# Audio_Input_Line_In.net
KiCad netlist of a schematic drawn in Altium Designer
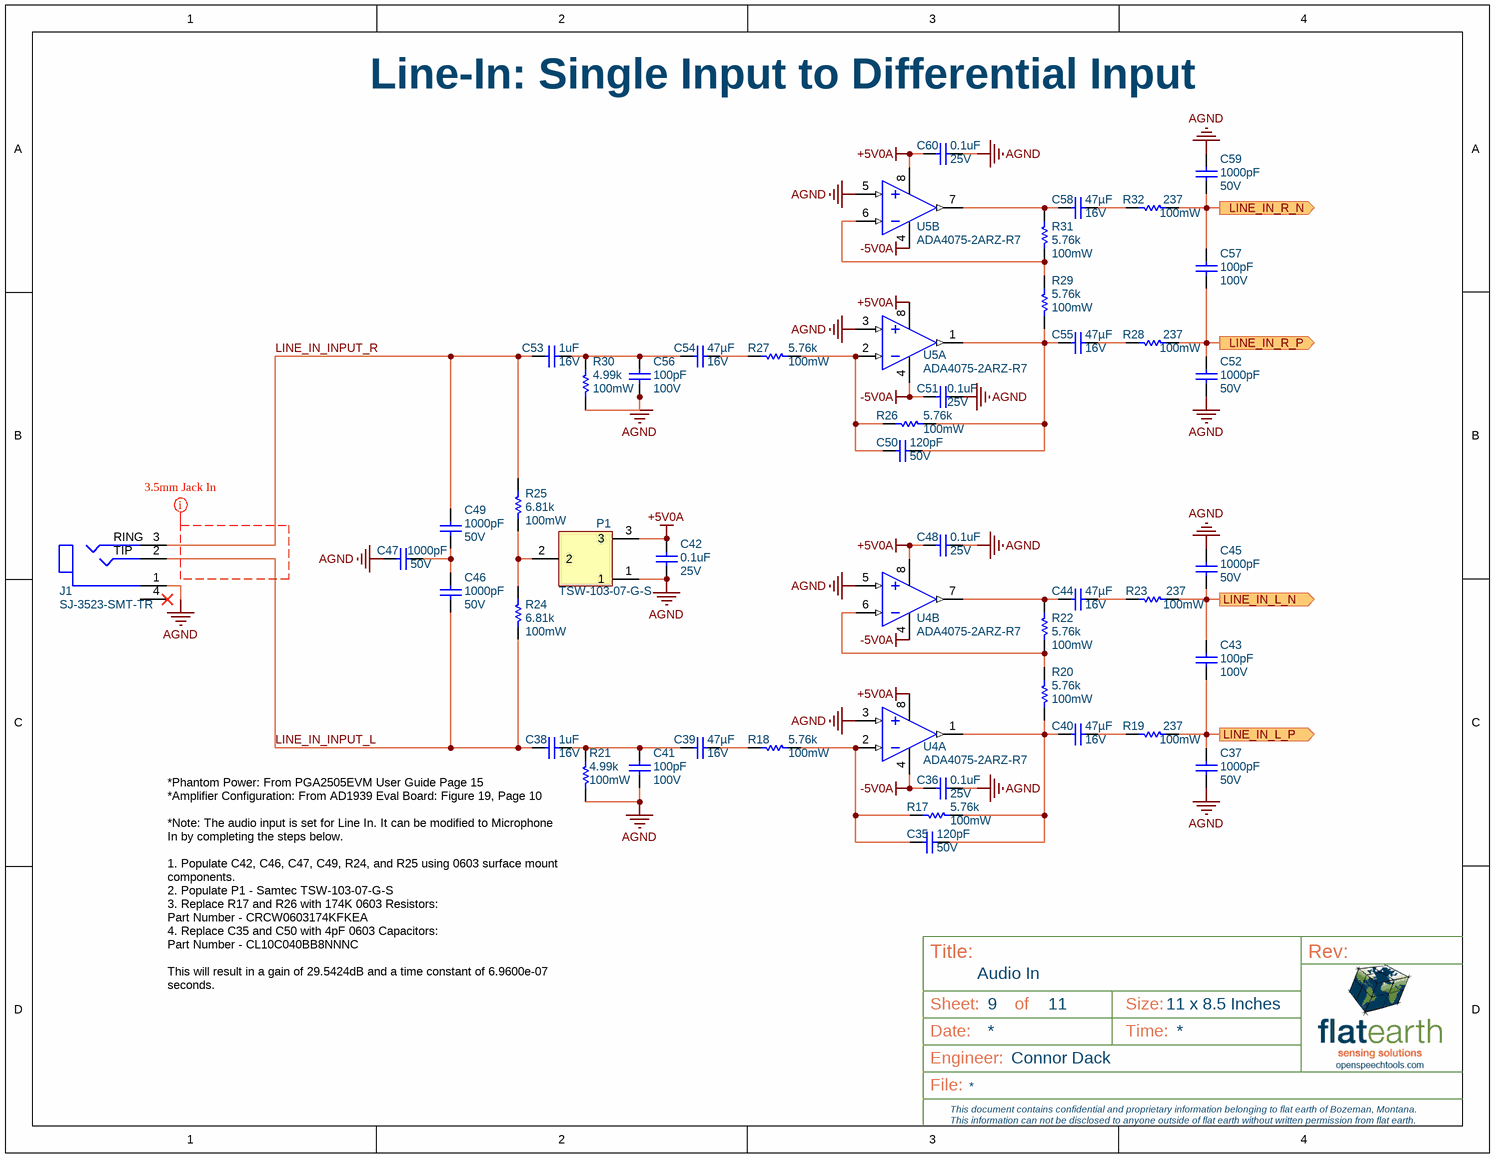
[diagram p0: Audio_Input_Line_In.SchDoc]

(export (version "E")
  (design (tool "Eeschema 10.0.6"))
  (components
    (comp (ref "C35")
      (value "CL10C121JB8NCNC")
      (footprint "3-0603_L")
      (description "120pF 50V Ceramic Capacitor C0G, NP0 0603 (1608 Metric) 0.063\" L x 0.031\" W (1.60mm x 0.80mm)")
      (fields
        (field (name "MANUFACTURER") "Samsung Electro-Mechanics America, Inc.")
        (field (name "TOLERANCE") "±5%")
        (field (name "VOLTAGE - RATED") "50V")
        (field (name "CAPACITANCE") "120pF")
      )
      (libsource (lib "Schematic_Components") (part "CL10C121JB8NCNC"))
    )
    (comp (ref "C36")
      (value "CGA3E2X7R1E104K080AA")
      (footprint "3-0603_L")
      (description "CAP CER 0.1UF 25V X7R 0603")
      (fields
        (field (name "MANUFACTURER") "TDK")
        (field (name "TOLERANCE") "10%")
        (field (name "VOLTAGE RATING") "25V")
        (field (name "CAPACITANCE") "0.1uF")
      )
      (libsource (lib "Schematic_Components_CD") (part "CGA3E2X7R1E104K080AA"))
    )
    (comp (ref "C37")
      (value "CL10B102KB8NNNC")
      (footprint "3-0603_L")
      (description "1000pF 50V Ceramic Capacitor X7R 0603 (1608 Metric) 0.063\" L x 0.031\" W (1.60mm x 0.80mm)")
      (fields
        (field (name "MANUFACTURER") "Samsung Electro-Mechanics America, Inc.")
        (field (name "TOLERANCE") "±10%")
        (field (name "VOLTAGE - RATED") "50V")
        (field (name "CAPACITANCE") "1000pF")
      )
      (libsource (lib "Schematic_Components") (part "CL10B102KB8NNNC"))
    )
    (comp (ref "C38")
      (value "CGA3E1X7R1C105M080AC")
      (footprint "3-0603_L")
      (description "CAP CER 1UF 16V X7R 0603")
      (fields
        (field (name "MANUFACTURER") "TDK")
        (field (name "TOLERANCE") "20%")
        (field (name "VOLTAGE RATING (DC)") "16V")
        (field (name "CAPACITANCE") "1uF")
      )
      (libsource (lib "Schematic_Components_CD") (part "CGA3E1X7R1C105M080AC"))
    )
    (comp (ref "C39")
      (value "GRM32EC81C476KE15L")
      (footprint "C1210X25_L")
      (description "47µF ±10% 16V Ceramic Capacitor X6S 1210 (3225 Metric)")
      (fields
        (field (name "MANUFACTURER") "Murata Electronics North America")
        (field (name "TOLERANCE") "±10%")
        (field (name "VOLTAGE - RATED") "16V")
        (field (name "CAPACITANCE") "47µF")
      )
      (libsource (lib "Schematic_Components") (part "GRM32EC81C476KE15L"))
    )
    (comp (ref "C40")
      (value "GRM32EC81C476KE15L")
      (footprint "C1210X25_L")
      (description "47µF ±10% 16V Ceramic Capacitor X6S 1210 (3225 Metric)")
      (fields
        (field (name "MANUFACTURER") "Murata Electronics North America")
        (field (name "TOLERANCE") "±10%")
        (field (name "VOLTAGE - RATED") "16V")
        (field (name "CAPACITANCE") "47µF")
      )
      (libsource (lib "Schematic_Components") (part "GRM32EC81C476KE15L"))
    )
    (comp (ref "C41")
      (value "C1608C0G2A101J")
      (footprint "3-0603_L")
      (description "CAP CER 100PF 100V 5% NP0 0603")
      (fields
        (field (name "MANUFACTURER") "TDK Corporation")
        (field (name "VOLTAGE - RATED") "100V")
        (field (name "TOLERANCE") "±5%")
        (field (name "CAPACITANCE") "100pF")
      )
      (libsource (lib "Schematic_Components") (part "C1608C0G2A101J"))
    )
    (comp (ref "C42")
      (value "CGA3E2X7R1E104K080AA")
      (footprint "3-0603_L")
      (description "CAP CER 0.1UF 25V X7R 0603")
      (fields
        (field (name "MANUFACTURER") "TDK")
        (field (name "TOLERANCE") "10%")
        (field (name "VOLTAGE RATING") "25V")
        (field (name "CAPACITANCE") "0.1uF")
      )
      (libsource (lib "Schematic_Components_CD") (part "CGA3E2X7R1E104K080AA"))
    )
    (comp (ref "C43")
      (value "C1608C0G2A101J")
      (footprint "3-0603_L")
      (description "CAP CER 100PF 100V 5% NP0 0603")
      (fields
        (field (name "MANUFACTURER") "TDK Corporation")
        (field (name "VOLTAGE - RATED") "100V")
        (field (name "TOLERANCE") "±5%")
        (field (name "CAPACITANCE") "100pF")
      )
      (libsource (lib "Schematic_Components") (part "C1608C0G2A101J"))
    )
    (comp (ref "C44")
      (value "GRM32EC81C476KE15L")
      (footprint "C1210X25_L")
      (description "47µF ±10% 16V Ceramic Capacitor X6S 1210 (3225 Metric)")
      (fields
        (field (name "MANUFACTURER") "Murata Electronics North America")
        (field (name "TOLERANCE") "±10%")
        (field (name "VOLTAGE - RATED") "16V")
        (field (name "CAPACITANCE") "47µF")
      )
      (libsource (lib "Schematic_Components") (part "GRM32EC81C476KE15L"))
    )
    (comp (ref "C45")
      (value "CL10B102KB8NNNC")
      (footprint "3-0603_L")
      (description "1000pF 50V Ceramic Capacitor X7R 0603 (1608 Metric) 0.063\" L x 0.031\" W (1.60mm x 0.80mm)")
      (fields
        (field (name "MANUFACTURER") "Samsung Electro-Mechanics America, Inc.")
        (field (name "TOLERANCE") "±10%")
        (field (name "VOLTAGE - RATED") "50V")
        (field (name "CAPACITANCE") "1000pF")
      )
      (libsource (lib "Schematic_Components") (part "CL10B102KB8NNNC"))
    )
    (comp (ref "C46")
      (value "C1608C0G1H102J")
      (footprint "3-0603_L_DNP")
      (description "CAP CER 1000PF 50V 5% NP0 0603")
      (fields
        (field (name "MANUFACTURER") "TDK Corporation")
        (field (name "VOLTAGE - RATED") "50V")
        (field (name "TOLERANCE") "±5%")
        (field (name "CAPACITANCE") "1000pF")
      )
      (libsource (lib "Schematic_Components") (part "C1608C0G1H102J"))
    )
    (comp (ref "C47")
      (value "C1608C0G1H102J")
      (footprint "3-0603_L_DNP")
      (description "CAP CER 1000PF 50V 5% NP0 0603")
      (fields
        (field (name "MANUFACTURER") "TDK Corporation")
        (field (name "VOLTAGE - RATED") "50V")
        (field (name "TOLERANCE") "±5%")
        (field (name "CAPACITANCE") "1000pF")
      )
      (libsource (lib "Schematic_Components") (part "C1608C0G1H102J"))
    )
    (comp (ref "C48")
      (value "CGA3E2X7R1E104K080AA")
      (footprint "3-0603_L")
      (description "CAP CER 0.1UF 25V X7R 0603")
      (fields
        (field (name "MANUFACTURER") "TDK")
        (field (name "TOLERANCE") "10%")
        (field (name "VOLTAGE RATING") "25V")
        (field (name "CAPACITANCE") "0.1uF")
      )
      (libsource (lib "Schematic_Components_CD") (part "CGA3E2X7R1E104K080AA"))
    )
    (comp (ref "C49")
      (value "C1608C0G1H102J")
      (footprint "3-0603_L_DNP")
      (description "CAP CER 1000PF 50V 5% NP0 0603")
      (fields
        (field (name "MANUFACTURER") "TDK Corporation")
        (field (name "VOLTAGE - RATED") "50V")
        (field (name "TOLERANCE") "±5%")
        (field (name "CAPACITANCE") "1000pF")
      )
      (libsource (lib "Schematic_Components") (part "C1608C0G1H102J"))
    )
    (comp (ref "C50")
      (value "CL10C121JB8NCNC")
      (footprint "3-0603_L")
      (description "120pF 50V Ceramic Capacitor C0G, NP0 0603 (1608 Metric) 0.063\" L x 0.031\" W (1.60mm x 0.80mm)")
      (fields
        (field (name "MANUFACTURER") "Samsung Electro-Mechanics America, Inc.")
        (field (name "TOLERANCE") "±5%")
        (field (name "VOLTAGE - RATED") "50V")
        (field (name "CAPACITANCE") "120pF")
      )
      (libsource (lib "Schematic_Components") (part "CL10C121JB8NCNC"))
    )
    (comp (ref "C51")
      (value "CGA3E2X7R1E104K080AA")
      (footprint "3-0603_L")
      (description "CAP CER 0.1UF 25V X7R 0603")
      (fields
        (field (name "MANUFACTURER") "TDK")
        (field (name "TOLERANCE") "10%")
        (field (name "VOLTAGE RATING") "25V")
        (field (name "CAPACITANCE") "0.1uF")
      )
      (libsource (lib "Schematic_Components_CD") (part "CGA3E2X7R1E104K080AA"))
    )
    (comp (ref "C52")
      (value "CL10B102KB8NNNC")
      (footprint "3-0603_L")
      (description "1000pF 50V Ceramic Capacitor X7R 0603 (1608 Metric) 0.063\" L x 0.031\" W (1.60mm x 0.80mm)")
      (fields
        (field (name "MANUFACTURER") "Samsung Electro-Mechanics America, Inc.")
        (field (name "TOLERANCE") "±10%")
        (field (name "VOLTAGE - RATED") "50V")
        (field (name "CAPACITANCE") "1000pF")
      )
      (libsource (lib "Schematic_Components") (part "CL10B102KB8NNNC"))
    )
    (comp (ref "C53")
      (value "CGA3E1X7R1C105M080AC")
      (footprint "3-0603_L")
      (description "CAP CER 1UF 16V X7R 0603")
      (fields
        (field (name "MANUFACTURER") "TDK")
        (field (name "TOLERANCE") "20%")
        (field (name "VOLTAGE RATING") "16V")
        (field (name "CAPACITANCE") "1uF")
      )
      (libsource (lib "Schematic_Components_CD") (part "CGA3E1X7R1C105M080AC"))
    )
    (comp (ref "C54")
      (value "GRM32EC81C476KE15L")
      (footprint "C1210X25_L")
      (description "47µF ±10% 16V Ceramic Capacitor X6S 1210 (3225 Metric)")
      (fields
        (field (name "MANUFACTURER") "Murata Electronics North America")
        (field (name "TOLERANCE") "±10%")
        (field (name "VOLTAGE - RATED") "16V")
        (field (name "CAPACITANCE") "47µF")
      )
      (libsource (lib "Schematic_Components") (part "GRM32EC81C476KE15L"))
    )
    (comp (ref "C55")
      (value "GRM32EC81C476KE15L")
      (footprint "C1210X25_L")
      (description "47µF ±10% 16V Ceramic Capacitor X6S 1210 (3225 Metric)")
      (fields
        (field (name "MANUFACTURER") "Murata Electronics North America")
        (field (name "TOLERANCE") "±10%")
        (field (name "VOLTAGE - RATED") "16V")
        (field (name "CAPACITANCE") "47µF")
      )
      (libsource (lib "Schematic_Components") (part "GRM32EC81C476KE15L"))
    )
    (comp (ref "C56")
      (value "C1608C0G2A101J")
      (footprint "3-0603_L")
      (description "CAP CER 100PF 100V 5% NP0 0603")
      (fields
        (field (name "MANUFACTURER") "TDK Corporation")
        (field (name "VOLTAGE - RATED") "100V")
        (field (name "TOLERANCE") "±5%")
        (field (name "CAPACITANCE") "100pF")
      )
      (libsource (lib "Schematic_Components") (part "C1608C0G2A101J"))
    )
    (comp (ref "C57")
      (value "C1608C0G2A101J")
      (footprint "3-0603_L")
      (description "CAP CER 100PF 100V 5% NP0 0603")
      (fields
        (field (name "MANUFACTURER") "TDK Corporation")
        (field (name "VOLTAGE - RATED") "100V")
        (field (name "TOLERANCE") "±5%")
        (field (name "CAPACITANCE") "100pF")
      )
      (libsource (lib "Schematic_Components") (part "C1608C0G2A101J"))
    )
    (comp (ref "C58")
      (value "GRM32EC81C476KE15L")
      (footprint "C1210X25_L")
      (description "47µF ±10% 16V Ceramic Capacitor X6S 1210 (3225 Metric)")
      (fields
        (field (name "MANUFACTURER") "Murata Electronics North America")
        (field (name "TOLERANCE") "±10%")
        (field (name "VOLTAGE - RATED") "16V")
        (field (name "CAPACITANCE") "47µF")
      )
      (libsource (lib "Schematic_Components") (part "GRM32EC81C476KE15L"))
    )
    (comp (ref "C59")
      (value "CL10B102KB8NNNC")
      (footprint "3-0603_L")
      (description "1000pF 50V Ceramic Capacitor X7R 0603 (1608 Metric) 0.063\" L x 0.031\" W (1.60mm x 0.80mm)")
      (fields
        (field (name "MANUFACTURER") "Samsung Electro-Mechanics America, Inc.")
        (field (name "TOLERANCE") "±10%")
        (field (name "VOLTAGE - RATED") "50V")
        (field (name "CAPACITANCE") "1000pF")
      )
      (libsource (lib "Schematic_Components") (part "CL10B102KB8NNNC"))
    )
    (comp (ref "C60")
      (value "CGA3E2X7R1E104K080AA")
      (footprint "3-0603_L")
      (description "CAP CER 0.1UF 25V X7R 0603")
      (fields
        (field (name "MANUFACTURER") "TDK")
        (field (name "TOLERANCE") "10%")
        (field (name "VOLTAGE RATING") "25V")
        (field (name "CAPACITANCE") "0.1uF")
      )
      (libsource (lib "Schematic_Components_CD") (part "CGA3E2X7R1E104K080AA"))
    )
    (comp (ref "J1")
      (value "SJ-3523-SMT-TR")
      (footprint "SJ-3523-SMT-TR")
      (description "3.50mm (0.141\", 1/8\", Mini Plug) - Headphone Phone Jack Stereo Connector Solder")
      (fields
        (field (name "MANUFACTURER") "CUI Inc.")
        (field (name "MANUFACTURER PART NUMBER") "SJ-3523-SMT-TR")
        (field (name "PUBLISHER") "Altium Limited")
      )
      (libsource (lib "Schematic_Components_CD") (part "SJ-3523-SMT-TR"))
    )
    (comp (ref "P1")
      (value "TSW-103-07-G-S")
      (footprint "3Pin_Header")
      (description "3 Pin Through Hole Connector with 0.1\" Spacing")
      (fields (field (name "MANUFACTURER") "Samtec") (field (name "PUBLISHER") "Altium Limited"))
      (libsource (lib "Schematic_Components_CD") (part "CONN_TH_3PIN_0D1"))
    )
    (comp (ref "R17")
      (value "ERJ-3EKF5761V")
      (footprint "3-0603_R_L")
      (description "RES SMD 5.76K OHM 1% 1/10W 0603")
      (fields
        (field (name "MANUFACTURER") "Panasonic Electronic Components")
        (field (name "TOLERANCE") "±1%")
        (field (name "POWER (WATTS)") "100mW")
        (field (name "RESISTANCE (OHMS)") "5.76k")
      )
      (libsource (lib "Schematic_Components") (part "ERJ-3EKF5761V"))
    )
    (comp (ref "R18")
      (value "ERJ-3EKF5761V")
      (footprint "3-0603_R_L")
      (description "RES SMD 5.76K OHM 1% 1/10W 0603")
      (fields
        (field (name "MANUFACTURER") "Panasonic Electronic Components")
        (field (name "TOLERANCE") "±1%")
        (field (name "POWER (WATTS)") "100mW")
        (field (name "RESISTANCE (OHMS)") "5.76k")
      )
      (libsource (lib "Schematic_Components") (part "ERJ-3EKF5761V"))
    )
    (comp (ref "R19")
      (value "ERJ-3EKF2370V")
      (footprint "3-0603_R_L")
      (description "RES SMD 237 OHM 1% 1/10W 0603")
      (fields
        (field (name "MANUFACTURER") "Panasonic Electronic Components")
        (field (name "TOLERANCE") "±1%")
        (field (name "POWER (WATTS)") "100mW")
        (field (name "RESISTANCE (OHMS)") "237")
      )
      (libsource (lib "Schematic_Components") (part "ERJ-3EKF2370V"))
    )
    (comp (ref "R20")
      (value "ERJ-3EKF5761V")
      (footprint "3-0603_R_L")
      (description "RES SMD 5.76K OHM 1% 1/10W 0603")
      (fields
        (field (name "MANUFACTURER") "Panasonic Electronic Components")
        (field (name "TOLERANCE") "±1%")
        (field (name "POWER (WATTS)") "100mW")
        (field (name "RESISTANCE (OHMS)") "5.76k")
      )
      (libsource (lib "Schematic_Components") (part "ERJ-3EKF5761V"))
    )
    (comp (ref "R21")
      (value "ERJ-3EKF4991V")
      (footprint "3-0603_R_L")
      (description "RES SMD 4.99K OHM 1% 1/10W 0603")
      (fields
        (field (name "MANUFACTURER") "Panasonic Electronic Components")
        (field (name "TOLERANCE") "±1%")
        (field (name "POWER (WATTS)") "100mW")
        (field (name "RESISTANCE (OHMS)") "4.99k")
      )
      (libsource (lib "Schematic_Components") (part "ERJ-3EKF4991V"))
    )
    (comp (ref "R22")
      (value "ERJ-3EKF5761V")
      (footprint "3-0603_R_L")
      (description "RES SMD 5.76K OHM 1% 1/10W 0603")
      (fields
        (field (name "MANUFACTURER") "Panasonic Electronic Components")
        (field (name "TOLERANCE") "±1%")
        (field (name "POWER (WATTS)") "100mW")
        (field (name "RESISTANCE (OHMS)") "5.76k")
      )
      (libsource (lib "Schematic_Components") (part "ERJ-3EKF5761V"))
    )
    (comp (ref "R23")
      (value "ERJ-3EKF2370V")
      (footprint "3-0603_R_L")
      (description "RES SMD 237 OHM 1% 1/10W 0603")
      (fields
        (field (name "MANUFACTURER") "Panasonic Electronic Components")
        (field (name "TOLERANCE") "±1%")
        (field (name "POWER (WATTS)") "100mW")
        (field (name "RESISTANCE (OHMS)") "237")
      )
      (libsource (lib "Schematic_Components") (part "ERJ-3EKF2370V"))
    )
    (comp (ref "R24")
      (value "ERJ-3EKF6811V")
      (footprint "3-0603_R_L_DNP")
      (description "RES SMD 6.81K OHM 1% 1/10W 0603")
      (fields
        (field (name "MANUFACTURER") "Panasonic ECG")
        (field (name "TOLERANCE") "1%")
        (field (name "POWER RATING") "100mW")
        (field (name "RESISTANCE") "6.81k")
      )
      (libsource (lib "Schematic_Components_CD") (part "ERJ-3EKF6811V"))
    )
    (comp (ref "R25")
      (value "ERJ-3EKF6811V")
      (footprint "3-0603_R_L_DNP")
      (description "RES SMD 6.81K OHM 1% 1/10W 0603")
      (fields
        (field (name "MANUFACTURER") "Panasonic ECG")
        (field (name "TOLERANCE") "1%")
        (field (name "POWER RATING") "100mW")
        (field (name "RESISTANCE") "6.81k")
      )
      (libsource (lib "Schematic_Components_CD") (part "ERJ-3EKF6811V"))
    )
    (comp (ref "R26")
      (value "ERJ-3EKF5761V")
      (footprint "3-0603_R_L")
      (description "RES SMD 5.76K OHM 1% 1/10W 0603")
      (fields
        (field (name "MANUFACTURER") "Panasonic Electronic Components")
        (field (name "TOLERANCE") "±1%")
        (field (name "POWER (WATTS)") "100mW")
        (field (name "RESISTANCE (OHMS)") "5.76k")
      )
      (libsource (lib "Schematic_Components") (part "ERJ-3EKF5761V"))
    )
    (comp (ref "R27")
      (value "ERJ-3EKF5761V")
      (footprint "3-0603_R_L")
      (description "RES SMD 5.76K OHM 1% 1/10W 0603")
      (fields
        (field (name "MANUFACTURER") "Panasonic Electronic Components")
        (field (name "TOLERANCE") "±1%")
        (field (name "POWER (WATTS)") "100mW")
        (field (name "RESISTANCE (OHMS)") "5.76k")
      )
      (libsource (lib "Schematic_Components") (part "ERJ-3EKF5761V"))
    )
    (comp (ref "R28")
      (value "ERJ-3EKF2370V")
      (footprint "3-0603_R_L")
      (description "RES SMD 237 OHM 1% 1/10W 0603")
      (fields
        (field (name "MANUFACTURER") "Panasonic Electronic Components")
        (field (name "TOLERANCE") "±1%")
        (field (name "POWER (WATTS)") "100mW")
        (field (name "RESISTANCE (OHMS)") "237")
      )
      (libsource (lib "Schematic_Components") (part "ERJ-3EKF2370V"))
    )
    (comp (ref "R29")
      (value "ERJ-3EKF5761V")
      (footprint "3-0603_R_L")
      (description "RES SMD 5.76K OHM 1% 1/10W 0603")
      (fields
        (field (name "MANUFACTURER") "Panasonic Electronic Components")
        (field (name "TOLERANCE") "±1%")
        (field (name "POWER (WATTS)") "100mW")
        (field (name "RESISTANCE (OHMS)") "5.76k")
      )
      (libsource (lib "Schematic_Components") (part "ERJ-3EKF5761V"))
    )
    (comp (ref "R30")
      (value "ERJ-3EKF4991V")
      (footprint "3-0603_R_L")
      (description "RES SMD 4.99K OHM 1% 1/10W 0603")
      (fields
        (field (name "MANUFACTURER") "Panasonic Electronic Components")
        (field (name "TOLERANCE") "±1%")
        (field (name "POWER (WATTS)") "100mW")
        (field (name "RESISTANCE (OHMS)") "4.99k")
      )
      (libsource (lib "Schematic_Components") (part "ERJ-3EKF4991V"))
    )
    (comp (ref "R31")
      (value "ERJ-3EKF5761V")
      (footprint "3-0603_R_L")
      (description "RES SMD 5.76K OHM 1% 1/10W 0603")
      (fields
        (field (name "MANUFACTURER") "Panasonic Electronic Components")
        (field (name "TOLERANCE") "±1%")
        (field (name "POWER (WATTS)") "100mW")
        (field (name "RESISTANCE (OHMS)") "5.76k")
      )
      (libsource (lib "Schematic_Components") (part "ERJ-3EKF5761V"))
    )
    (comp (ref "R32")
      (value "ERJ-3EKF2370V")
      (footprint "3-0603_R_L")
      (description "RES SMD 237 OHM 1% 1/10W 0603")
      (fields
        (field (name "MANUFACTURER") "Panasonic Electronic Components")
        (field (name "TOLERANCE") "±1%")
        (field (name "POWER (WATTS)") "100mW")
        (field (name "RESISTANCE (OHMS)") "237")
      )
      (libsource (lib "Schematic_Components") (part "ERJ-3EKF2370V"))
    )
    (comp (ref "U4")
      (value "ADA4075-2ARZ-R7")
      (footprint "SOIC127P600X175-8N")
      (description "IC OPAMP GP 6.5MHZ 8SOIC")
      (fields
        (field (name "MANUFACTURER") "Analog Devices Inc.")
        (field (name "MANUFACTURER PART NUMBER") "ADA4075-2ARZ-R7")
      )
      (libsource (lib "Schematic_Components_CD") (part "ADA4075-2ARZ-R7"))
    )
    (comp (ref "U5")
      (value "ADA4075-2ARZ-R7")
      (footprint "SOIC127P600X175-8N")
      (description "IC OPAMP GP 6.5MHZ 8SOIC")
      (fields
        (field (name "MANUFACTURER") "Analog Devices Inc.")
        (field (name "MANUFACTURER PART NUMBER") "ADA4075-2ARZ-R7")
      )
      (libsource (lib "Schematic_Components_CD") (part "ADA4075-2ARZ-R7"))
    )
  )
  (nets
    (net (code "1") (name "+5V0A") (class "Default")
      (node (ref "C42") (pin "2") (pinfunction "2_2") (pintype "passive"))
      (node (ref "C48") (pin "2") (pinfunction "2_2") (pintype "passive"))
      (node (ref "C60") (pin "2") (pinfunction "2_2") (pintype "passive"))
      (node (ref "P1") (pin "3") (pinfunction "3_3") (pintype "passive"))
      (node (ref "U4") (pin "8") (pinfunction "V+_8") (pintype "passive"))
      (node (ref "U5") (pin "8") (pinfunction "V+_8") (pintype "passive"))
    )
    (net (code "2") (name "-5V0A") (class "Default")
      (node (ref "C36") (pin "2") (pinfunction "2_2") (pintype "passive"))
      (node (ref "C51") (pin "2") (pinfunction "2_2") (pintype "passive"))
      (node (ref "U4") (pin "4") (pinfunction "V-_4") (pintype "power_in"))
      (node (ref "U5") (pin "4") (pinfunction "V-_4") (pintype "power_in"))
    )
    (net (code "3") (name "/LINE_IN_INPUT_L") (class "Default")
      (node (ref "C38") (pin "1") (pinfunction "1_1") (pintype "passive"))
      (node (ref "C46") (pin "2") (pinfunction "2_2") (pintype "passive"))
      (node (ref "J1") (pin "2") (pinfunction "Tip_2") (pintype "passive"))
      (node (ref "R24") (pin "2") (pinfunction "2_2") (pintype "passive"))
    )
    (net (code "4") (name "/LINE_IN_INPUT_R") (class "Default")
      (node (ref "C49") (pin "1") (pinfunction "1_1") (pintype "passive"))
      (node (ref "C53") (pin "1") (pinfunction "1_1") (pintype "passive"))
      (node (ref "J1") (pin "3") (pinfunction "Ring_3") (pintype "passive"))
      (node (ref "R25") (pin "1") (pinfunction "1_1") (pintype "passive"))
    )
    (net (code "5") (name "/LINE_IN_L_N") (class "Default")
      (node (ref "C43") (pin "1") (pinfunction "1_1") (pintype "passive"))
      (node (ref "C45") (pin "2") (pinfunction "2_2") (pintype "passive"))
      (node (ref "R23") (pin "2") (pinfunction "2_2") (pintype "passive"))
    )
    (net (code "6") (name "/LINE_IN_L_P") (class "Default")
      (node (ref "C37") (pin "2") (pinfunction "2_2") (pintype "passive"))
      (node (ref "C43") (pin "2") (pinfunction "2_2") (pintype "passive"))
      (node (ref "R19") (pin "2") (pinfunction "2_2") (pintype "passive"))
    )
    (net (code "7") (name "/LINE_IN_R_N") (class "Default")
      (node (ref "C57") (pin "1") (pinfunction "1_1") (pintype "passive"))
      (node (ref "C59") (pin "2") (pinfunction "2_2") (pintype "passive"))
      (node (ref "R32") (pin "2") (pinfunction "2_2") (pintype "passive"))
    )
    (net (code "8") (name "/LINE_IN_R_P") (class "Default")
      (node (ref "C52") (pin "2") (pinfunction "2_2") (pintype "passive"))
      (node (ref "C57") (pin "2") (pinfunction "2_2") (pintype "passive"))
      (node (ref "R28") (pin "2") (pinfunction "2_2") (pintype "passive"))
    )
    (net (code "9") (name "AGND") (class "Default")
      (node (ref "C36") (pin "1") (pinfunction "1_1") (pintype "passive"))
      (node (ref "C37") (pin "1") (pinfunction "1_1") (pintype "passive"))
      (node (ref "C41") (pin "2") (pinfunction "2_2") (pintype "passive"))
      (node (ref "C42") (pin "1") (pinfunction "1_1") (pintype "passive"))
      (node (ref "C45") (pin "1") (pinfunction "1_1") (pintype "passive"))
      (node (ref "C47") (pin "2") (pinfunction "2_2") (pintype "passive"))
      (node (ref "C48") (pin "1") (pinfunction "1_1") (pintype "passive"))
      (node (ref "C51") (pin "1") (pinfunction "1_1") (pintype "passive"))
      (node (ref "C52") (pin "1") (pinfunction "1_1") (pintype "passive"))
      (node (ref "C56") (pin "2") (pinfunction "2_2") (pintype "passive"))
      (node (ref "C59") (pin "1") (pinfunction "1_1") (pintype "passive"))
      (node (ref "C60") (pin "1") (pinfunction "1_1") (pintype "passive"))
      (node (ref "J1") (pin "1") (pinfunction "Sleeve_1") (pintype "passive"))
      (node (ref "P1") (pin "1") (pinfunction "1_1") (pintype "passive"))
      (node (ref "R21") (pin "1") (pinfunction "1_1") (pintype "passive"))
      (node (ref "R30") (pin "1") (pinfunction "1_1") (pintype "passive"))
      (node (ref "U4") (pin "3") (pinfunction "+INA_3") (pintype "input"))
      (node (ref "U4") (pin "5") (pinfunction "+INB_5") (pintype "input"))
      (node (ref "U5") (pin "3") (pinfunction "+INA_3") (pintype "input"))
      (node (ref "U5") (pin "5") (pinfunction "+INB_5") (pintype "input"))
    )
    (net (code "10") (name "Net-(C38-Pad2)") (class "Default")
      (node (ref "C38") (pin "2") (pinfunction "2_2") (pintype "passive"))
      (node (ref "C39") (pin "1") (pinfunction "1_1") (pintype "passive"))
      (node (ref "C41") (pin "1") (pinfunction "1_1") (pintype "passive"))
      (node (ref "R21") (pin "2") (pinfunction "2_2") (pintype "passive"))
    )
    (net (code "11") (name "Net-(C39-Pad2)") (class "Default")
      (node (ref "C39") (pin "2") (pinfunction "2_2") (pintype "passive"))
      (node (ref "R18") (pin "1") (pinfunction "1_1") (pintype "passive"))
    )
    (net (code "12") (name "Net-(C40-Pad2)") (class "Default")
      (node (ref "C40") (pin "2") (pinfunction "2_2") (pintype "passive"))
      (node (ref "R19") (pin "1") (pinfunction "1_1") (pintype "passive"))
    )
    (net (code "13") (name "Net-(C44-Pad2)") (class "Default")
      (node (ref "C44") (pin "2") (pinfunction "2_2") (pintype "passive"))
      (node (ref "R23") (pin "1") (pinfunction "1_1") (pintype "passive"))
    )
    (net (code "14") (name "Net-(C46-Pad1)") (class "Default")
      (node (ref "C46") (pin "1") (pinfunction "1_1") (pintype "passive"))
      (node (ref "C47") (pin "1") (pinfunction "1_1") (pintype "passive"))
      (node (ref "C49") (pin "2") (pinfunction "2_2") (pintype "passive"))
    )
    (net (code "15") (name "Net-(C53-Pad2)") (class "Default")
      (node (ref "C53") (pin "2") (pinfunction "2_2") (pintype "passive"))
      (node (ref "C54") (pin "1") (pinfunction "1_1") (pintype "passive"))
      (node (ref "C56") (pin "1") (pinfunction "1_1") (pintype "passive"))
      (node (ref "R30") (pin "2") (pinfunction "2_2") (pintype "passive"))
    )
    (net (code "16") (name "Net-(C54-Pad2)") (class "Default")
      (node (ref "C54") (pin "2") (pinfunction "2_2") (pintype "passive"))
      (node (ref "R27") (pin "1") (pinfunction "1_1") (pintype "passive"))
    )
    (net (code "17") (name "Net-(C55-Pad2)") (class "Default")
      (node (ref "C55") (pin "2") (pinfunction "2_2") (pintype "passive"))
      (node (ref "R28") (pin "1") (pinfunction "1_1") (pintype "passive"))
    )
    (net (code "18") (name "Net-(C58-Pad2)") (class "Default")
      (node (ref "C58") (pin "2") (pinfunction "2_2") (pintype "passive"))
      (node (ref "R32") (pin "1") (pinfunction "1_1") (pintype "passive"))
    )
    (net (code "19") (name "Net-(P1-Pad2)") (class "Default")
      (node (ref "P1") (pin "2") (pinfunction "2_2") (pintype "passive"))
      (node (ref "R24") (pin "1") (pinfunction "1_1") (pintype "passive"))
      (node (ref "R25") (pin "2") (pinfunction "2_2") (pintype "passive"))
    )
    (net (code "20") (name "Net-(U4A--INA)") (class "Default")
      (node (ref "C35") (pin "1") (pinfunction "1_1") (pintype "passive"))
      (node (ref "R17") (pin "1") (pinfunction "1_1") (pintype "passive"))
      (node (ref "R18") (pin "2") (pinfunction "2_2") (pintype "passive"))
      (node (ref "U4") (pin "2") (pinfunction "-INA_2") (pintype "input"))
    )
    (net (code "21") (name "Net-(U4A-OUTA)") (class "Default")
      (node (ref "C35") (pin "2") (pinfunction "2_2") (pintype "passive"))
      (node (ref "C40") (pin "1") (pinfunction "1_1") (pintype "passive"))
      (node (ref "R17") (pin "2") (pinfunction "2_2") (pintype "passive"))
      (node (ref "R20") (pin "1") (pinfunction "1_1") (pintype "passive"))
      (node (ref "U4") (pin "1") (pinfunction "OUTA_1") (pintype "output"))
    )
    (net (code "22") (name "Net-(U4B--INB)") (class "Default")
      (node (ref "R20") (pin "2") (pinfunction "2_2") (pintype "passive"))
      (node (ref "R22") (pin "1") (pinfunction "1_1") (pintype "passive"))
      (node (ref "U4") (pin "6") (pinfunction "-INB_6") (pintype "input"))
    )
    (net (code "23") (name "Net-(U4B-OUTB)") (class "Default")
      (node (ref "C44") (pin "1") (pinfunction "1_1") (pintype "passive"))
      (node (ref "R22") (pin "2") (pinfunction "2_2") (pintype "passive"))
      (node (ref "U4") (pin "7") (pinfunction "OUTB_7") (pintype "output"))
    )
    (net (code "24") (name "Net-(U5A--INA)") (class "Default")
      (node (ref "C50") (pin "2") (pinfunction "2_2") (pintype "passive"))
      (node (ref "R26") (pin "1") (pinfunction "1_1") (pintype "passive"))
      (node (ref "R27") (pin "2") (pinfunction "2_2") (pintype "passive"))
      (node (ref "U5") (pin "2") (pinfunction "-INA_2") (pintype "input"))
    )
    (net (code "25") (name "Net-(U5A-OUTA)") (class "Default")
      (node (ref "C50") (pin "1") (pinfunction "1_1") (pintype "passive"))
      (node (ref "C55") (pin "1") (pinfunction "1_1") (pintype "passive"))
      (node (ref "R26") (pin "2") (pinfunction "2_2") (pintype "passive"))
      (node (ref "R29") (pin "1") (pinfunction "1_1") (pintype "passive"))
      (node (ref "U5") (pin "1") (pinfunction "OUTA_1") (pintype "output"))
    )
    (net (code "26") (name "Net-(U5B--INB)") (class "Default")
      (node (ref "R29") (pin "2") (pinfunction "2_2") (pintype "passive"))
      (node (ref "R31") (pin "1") (pinfunction "1_1") (pintype "passive"))
      (node (ref "U5") (pin "6") (pinfunction "-INB_6") (pintype "input"))
    )
    (net (code "27") (name "Net-(U5B-OUTB)") (class "Default")
      (node (ref "C58") (pin "1") (pinfunction "1_1") (pintype "passive"))
      (node (ref "R31") (pin "2") (pinfunction "2_2") (pintype "passive"))
      (node (ref "U5") (pin "7") (pinfunction "OUTB_7") (pintype "output"))
    )
    (net (code "28") (name "unconnected-(J1-NC-Pad4)") (class "Default")
      (node (ref "J1") (pin "4") (pinfunction "NC_4") (pintype "passive+no_connect"))
    )
  )
)
